# AD.net
KiCad netlist of a schematic drawn in Altium Designer
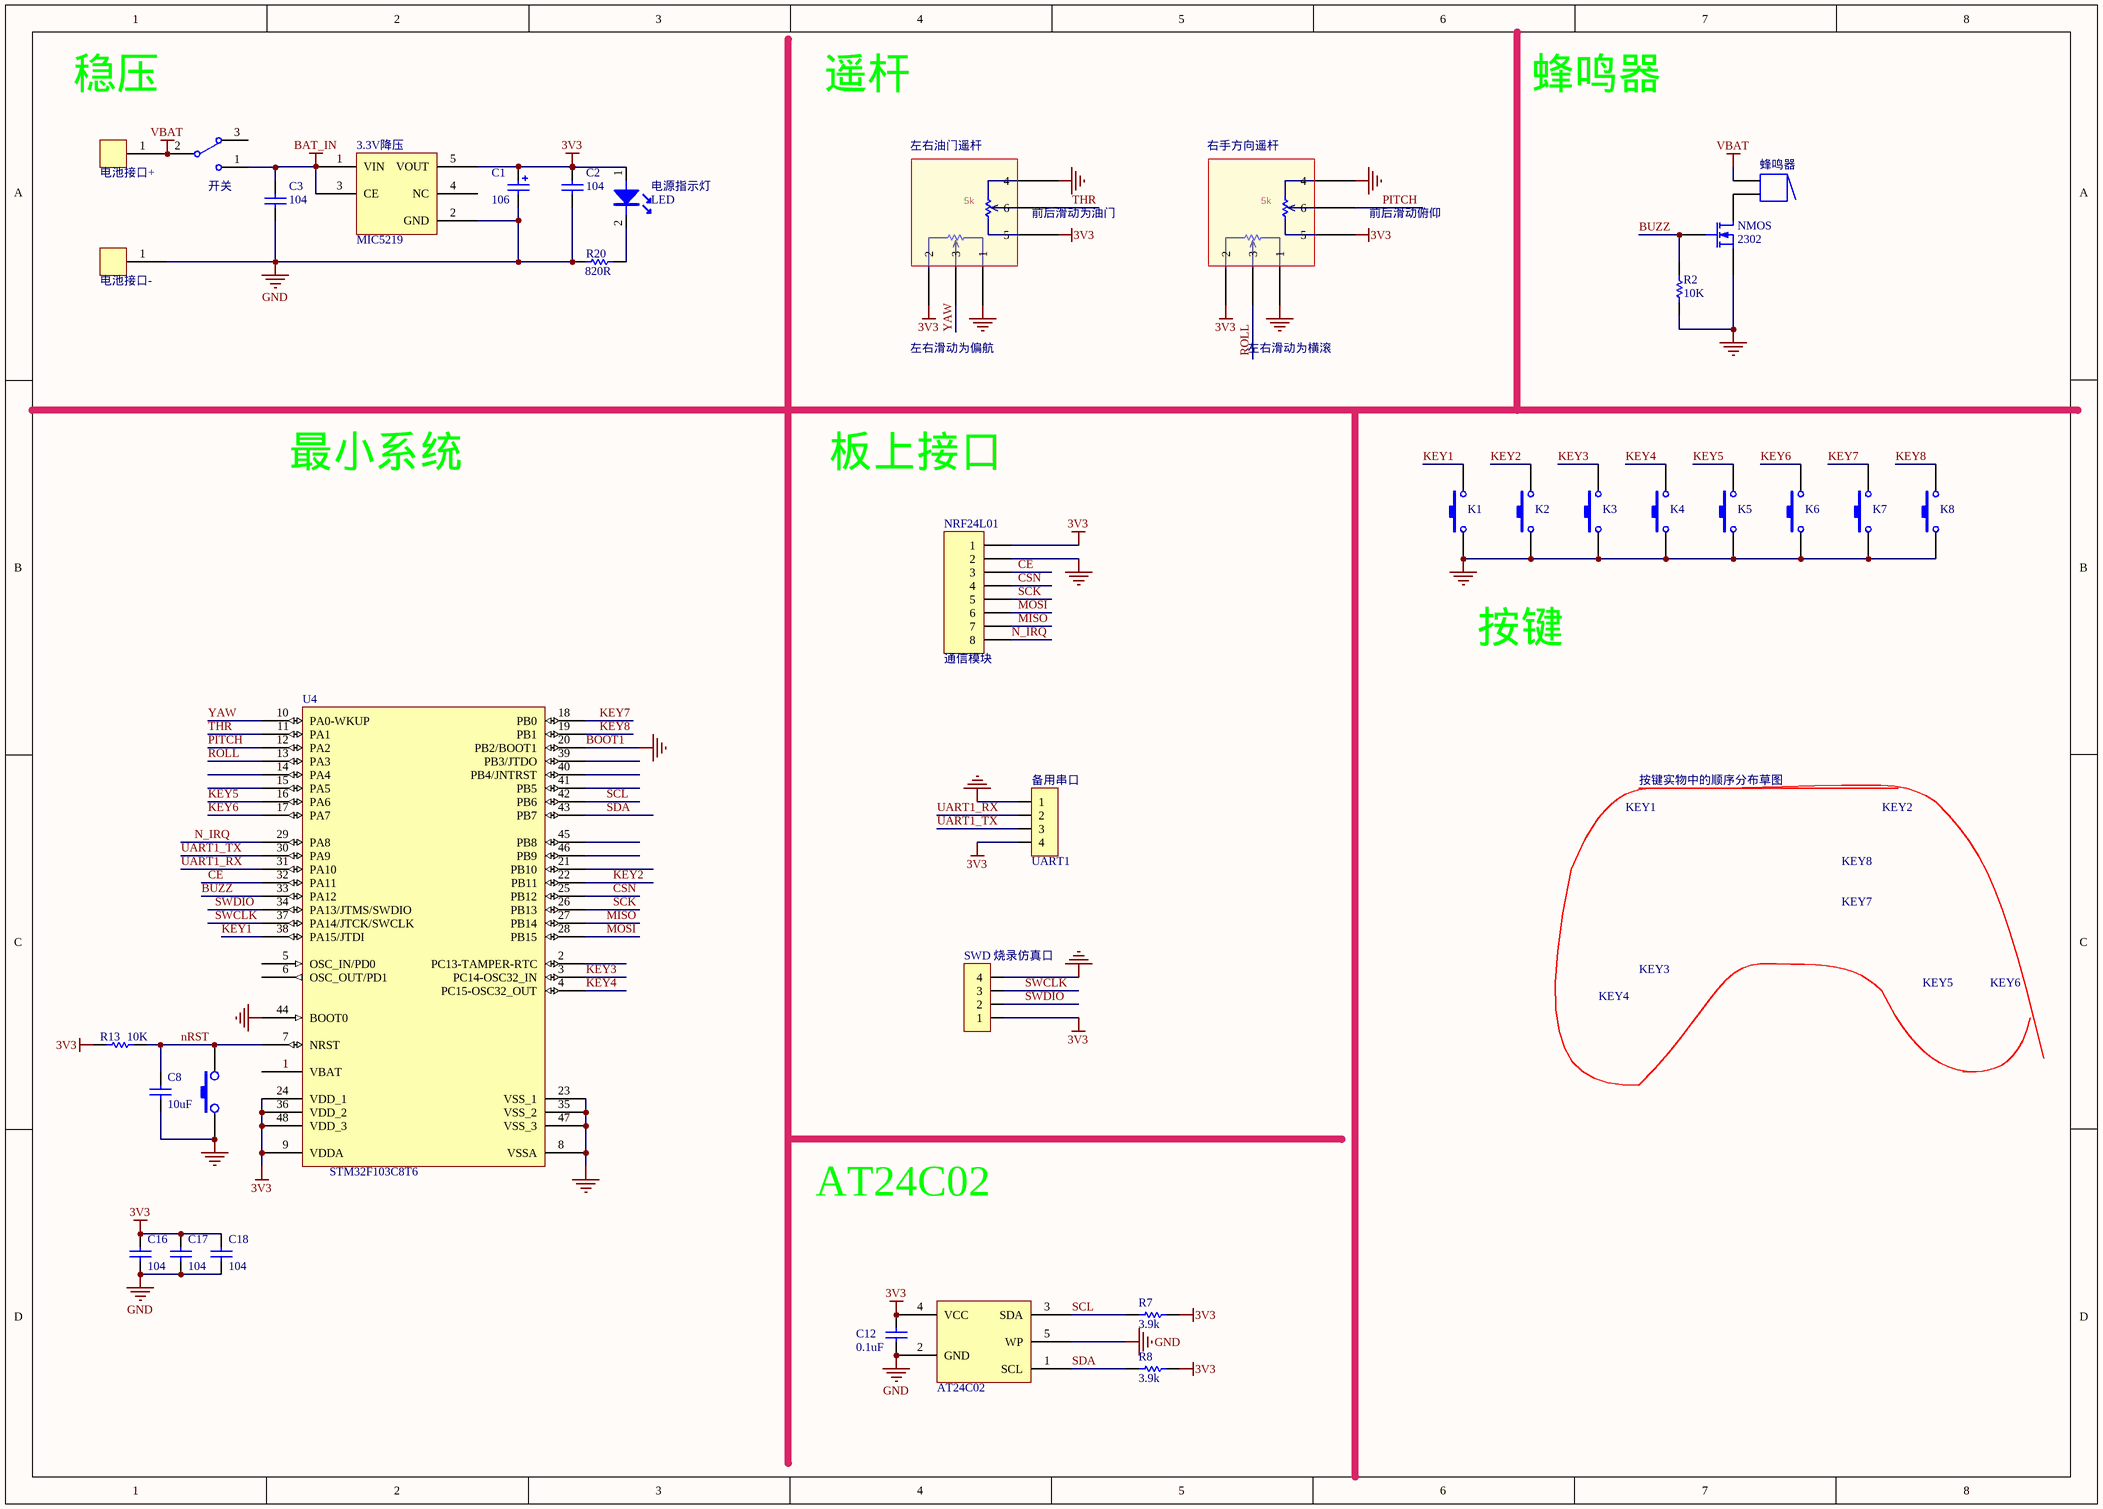
[diagram p0: 遥控原理图（AD打开）.SchDoc]

(export (version "E")
  (design (tool "Eeschema 10.0.6"))
  (components
    (comp (ref "*1") (value "AT24C02") (footprint "SOT23-5") (libsource (lib "开源小遥控") (part "AT24C02")))
    (comp (ref "3.3V降压")
      (value "MIC5219")
      (footprint "SOT23-5")
      (libsource (lib "quadrotor") (part "HT7X33"))
    )
    (comp (ref "C1")
      (value "106")
      (footprint "1206")
      (description "Polarized Capacitor (Radial)")
      (fields
        (field (name "VOLTAGE") "16V")
        (field (name "Comment") "Cap Tan A")
        (field (name "PUBLISHER") "Altium Limited")
      )
      (libsource (lib "ChapuIntegratedLibrary") (part "Cap Tan A"))
    )
    (comp (ref "C2")
      (value "104")
      (footprint "1206_C")
      (description "Polarized Capacitor (Radial)")
      (fields (field (name "Comment") "Cap Chip 1206") (field (name "PUBLISHER") "Altium Limited"))
      (libsource (lib "ChapuIntegratedLibrary") (part "Cap Chip 1206"))
    )
    (comp (ref "C3")
      (value "104")
      (footprint "0603_C")
      (description "Polarized Capacitor (Radial)")
      (fields (field (name "Comment") "Cap Chip 1206") (field (name "PUBLISHER") "Altium Limited"))
      (libsource (lib "ChapuIntegratedLibrary") (part "Cap Chip 1206"))
    )
    (comp (ref "C8") (value "10uF") (footprint "0603_C") (libsource (lib "1218迷你四轴工程_1") (part "C0603")))
    (comp (ref "C12")
      (value "0.1uF")
      (footprint "0603C")
      (description "Capacitor")
      (fields (field (name "Comment") "Cap") (field (name "PUBLISHER") "Altium Limited"))
      (libsource (lib "Miscellaneous Devices") (part "Cap"))
    )
    (comp (ref "C16") (value "104") (footprint "0603_C") (libsource (lib "1218迷你四轴工程_1") (part "C0603")))
    (comp (ref "C17") (value "104") (footprint "0603_C") (libsource (lib "1218迷你四轴工程_1") (part "C0603")))
    (comp (ref "C18") (value "104") (footprint "0603_C") (libsource (lib "1218迷你四轴工程_1") (part "C0603")))
    (comp (ref "K1")
      (value "40%（油門上限）")
      (footprint "4脚贴片点动开关")
      (description "Switch")
      (fields (field (name "PUBLISHER") "Altium Limited"))
      (libsource (lib "Miscellaneous Devices") (part "SW-PB"))
    )
    (comp (ref "K2")
      (value "60%")
      (footprint "4脚贴片点动开关")
      (description "Switch")
      (fields (field (name "PUBLISHER") "Altium Limited"))
      (libsource (lib "Miscellaneous Devices") (part "SW-PB"))
    )
    (comp (ref "K3")
      (value "40%（油門上限）")
      (footprint "4脚贴片点动开关")
      (description "Switch")
      (fields (field (name "PUBLISHER") "Altium Limited"))
      (libsource (lib "Miscellaneous Devices") (part "SW-PB"))
    )
    (comp (ref "K4")
      (value "60%")
      (footprint "4脚贴片点动开关")
      (description "Switch")
      (fields (field (name "PUBLISHER") "Altium Limited"))
      (libsource (lib "Miscellaneous Devices") (part "SW-PB"))
    )
    (comp (ref "K5")
      (value "40%（油門上限）")
      (footprint "4脚贴片点动开关")
      (description "Switch")
      (fields (field (name "PUBLISHER") "Altium Limited"))
      (libsource (lib "Miscellaneous Devices") (part "SW-PB"))
    )
    (comp (ref "K6")
      (value "60%")
      (footprint "4脚贴片点动开关")
      (description "Switch")
      (fields (field (name "PUBLISHER") "Altium Limited"))
      (libsource (lib "Miscellaneous Devices") (part "SW-PB"))
    )
    (comp (ref "K7")
      (value "40%（油門上限）")
      (footprint "4脚贴片点动开关")
      (description "Switch")
      (fields (field (name "PUBLISHER") "Altium Limited"))
      (libsource (lib "Miscellaneous Devices") (part "SW-PB"))
    )
    (comp (ref "K8")
      (value "60%")
      (footprint "4脚贴片点动开关")
      (description "Switch")
      (fields (field (name "PUBLISHER") "Altium Limited"))
      (libsource (lib "Miscellaneous Devices") (part "SW-PB"))
    )
    (comp (ref "NMOS")
      (value "2302")
      (footprint "SOT-23-3")
      (description "N-Channel MOSFET")
      (fields (field (name "PUBLISHER") "Altium Limited"))
      (libsource (lib "Miscellaneous Devices") (part "MOSFET-N"))
    )
    (comp (ref "NRF24L01")
      (value "通信模块")
      (footprint "HDR1X8")
      (description "Header, 8-Pin")
      (fields (field (name "PUBLISHER") "Altium Limited"))
      (libsource (lib "Miscellaneous Connectors") (part "Header 8"))
    )
    (comp (ref "R2")
      (value "10K")
      (footprint "0603_R")
      (description "Resistor")
      (fields (field (name "Comment") "222") (field (name "PUBLISHER") "Altium Limited"))
      (libsource (lib "Miscellaneous Devices") (part "Res1"))
    )
    (comp (ref "R7")
      (value "3.9k")
      (footprint "0603R")
      (description "Resistor")
      (fields (field (name "Comment") "222") (field (name "PUBLISHER") "Altium Limited"))
      (libsource (lib "Miscellaneous Devices") (part "Res1"))
    )
    (comp (ref "R8")
      (value "3.9k")
      (footprint "0603R")
      (description "Resistor")
      (fields (field (name "Comment") "222") (field (name "PUBLISHER") "Altium Limited"))
      (libsource (lib "Miscellaneous Devices") (part "Res1"))
    )
    (comp (ref "R13")
      (value "10K")
      (footprint "0603_R")
      (description "Resistor")
      (fields (field (name "Comment") "Res1") (field (name "PUBLISHER") "Altium Limited"))
      (libsource (lib "Miscellaneous Devices") (part "Res1"))
    )
    (comp (ref "R20")
      (value "820R")
      (footprint "0603_R")
      (description "Resistor")
      (fields (field (name "Comment") "222") (field (name "PUBLISHER") "Altium Limited"))
      (libsource (lib "Miscellaneous Devices") (part "Res1"))
    )
    (comp (ref "REST1") (value "SW-PB") (footprint "SW-2") (libsource (lib "SW开关") (part "SW-PB")))
    (comp (ref "SWD 烧录仿真口")
      (value "SWD")
      (footprint "1.27侧卧表贴")
      (description "Header, 4-Pin, Right Angle")
      (fields (field (name "PUBLISHER") "Altium Limited"))
      (libsource (lib "linch051") (part "Header 4H"))
    )
    (comp (ref "U4")
      (value "STM32F103C8T6")
      (footprint "LQFP48")
      (libsource (lib "微型四轴") (part "STM32F103C8T6"))
    )
    (comp (ref "右手方向遥杆") (value "摇杆") (footprint "遥控电位器") (libsource (lib "开源小遥控") (part "摇杆")))
    (comp (ref "备用串口")
      (value "UART1")
      (footprint "1.27侧卧表贴")
      (description "Header, 4-Pin, Right Angle")
      (fields (field (name "PUBLISHER") "Altium Limited"))
      (libsource (lib "") (part "Header 4H_1"))
    )
    (comp (ref "左右油门遥杆") (value "摇杆") (footprint "遥控电位器") (libsource (lib "开源小遥控") (part "摇杆")))
    (comp (ref "开关")
      (value "SW-SPDT")
      (footprint "SW-5")
      (description "SPDT Subminiature Toggle Switch, Right Angle Mounting, Vertical Actuation")
      (fields (field (name "PUBLISHER") "Altium Limited"))
      (libsource (lib "Miscellaneous Devices") (part "SW-SPDT"))
    )
    (comp (ref "电池接口+") (value "Header 1") (footprint "BAT") (libsource (lib "quadrotor") (part "Header 1")))
    (comp (ref "电池接口-") (value "Header 1") (footprint "BAT") (libsource (lib "quadrotor") (part "Header 1")))
    (comp (ref "电源指示灯") (value "LED") (footprint "0603_LED") (libsource (lib "1218迷你四轴工程_1") (part "LED")))
    (comp (ref "蜂鸣器")
      (value "Buzzer")
      (footprint "蜂鸣器9mm")
      (description "Magnetic Transducer Buzzer")
      (fields (field (name "PUBLISHER") "Altium Limited"))
      (libsource (lib "PCB_Project1") (part "Buzzer"))
    )
  )
  (nets
    (net (code "1") (name "/BUZZ") (class "Default")
      (node (ref "NMOS") (pin "2") (pinfunction "G_2") (pintype "passive"))
      (node (ref "R2") (pin "1") (pinfunction "1_1") (pintype "passive"))
      (node (ref "U4") (pin "33") (pinfunction "PA12_33") (pintype "bidirectional"))
    )
    (net (code "2") (name "/CE") (class "Default")
      (node (ref "NRF24L01") (pin "3") (pinfunction "3_3") (pintype "passive"))
      (node (ref "U4") (pin "32") (pinfunction "PA11_32") (pintype "bidirectional"))
    )
    (net (code "3") (name "/CSN") (class "Default")
      (node (ref "NRF24L01") (pin "4") (pinfunction "4_4") (pintype "passive"))
      (node (ref "U4") (pin "25") (pinfunction "PB12_25") (pintype "bidirectional"))
    )
    (net (code "4") (name "/KEY1") (class "Default")
      (node (ref "K1") (pin "2") (pinfunction "2_2") (pintype "passive"))
      (node (ref "U4") (pin "38") (pinfunction "PA15/JTDI_38") (pintype "bidirectional"))
    )
    (net (code "5") (name "/KEY2") (class "Default")
      (node (ref "K2") (pin "2") (pinfunction "2_2") (pintype "passive"))
      (node (ref "U4") (pin "22") (pinfunction "PB11_22") (pintype "bidirectional"))
    )
    (net (code "6") (name "/KEY3") (class "Default")
      (node (ref "K3") (pin "2") (pinfunction "2_2") (pintype "passive"))
      (node (ref "U4") (pin "3") (pinfunction "PC14-OSC32_IN_3") (pintype "bidirectional"))
    )
    (net (code "7") (name "/KEY4") (class "Default")
      (node (ref "K4") (pin "2") (pinfunction "2_2") (pintype "passive"))
      (node (ref "U4") (pin "4") (pinfunction "PC15-OSC32_OUT_4") (pintype "bidirectional"))
    )
    (net (code "8") (name "/KEY5") (class "Default")
      (node (ref "K5") (pin "2") (pinfunction "2_2") (pintype "passive"))
      (node (ref "U4") (pin "16") (pinfunction "PA6_16") (pintype "bidirectional"))
    )
    (net (code "9") (name "/KEY6") (class "Default")
      (node (ref "K6") (pin "2") (pinfunction "2_2") (pintype "passive"))
      (node (ref "U4") (pin "17") (pinfunction "PA7_17") (pintype "bidirectional"))
    )
    (net (code "10") (name "/KEY7") (class "Default")
      (node (ref "K7") (pin "2") (pinfunction "2_2") (pintype "passive"))
      (node (ref "U4") (pin "18") (pinfunction "PB0_18") (pintype "bidirectional"))
    )
    (net (code "11") (name "/KEY8") (class "Default")
      (node (ref "K8") (pin "2") (pinfunction "2_2") (pintype "passive"))
      (node (ref "U4") (pin "19") (pinfunction "PB1_19") (pintype "bidirectional"))
    )
    (net (code "12") (name "/MISO") (class "Default")
      (node (ref "NRF24L01") (pin "7") (pinfunction "7_7") (pintype "passive"))
      (node (ref "U4") (pin "27") (pinfunction "PB14_27") (pintype "bidirectional"))
    )
    (net (code "13") (name "/MOSI") (class "Default")
      (node (ref "NRF24L01") (pin "6") (pinfunction "6_6") (pintype "passive"))
      (node (ref "U4") (pin "28") (pinfunction "PB15_28") (pintype "bidirectional"))
    )
    (net (code "14") (name "/N_IRQ") (class "Default")
      (node (ref "NRF24L01") (pin "8") (pinfunction "8_8") (pintype "passive"))
      (node (ref "U4") (pin "29") (pinfunction "PA8_29") (pintype "bidirectional"))
    )
    (net (code "15") (name "/PITCH") (class "Default")
      (node (ref "U4") (pin "12") (pinfunction "PA2_12") (pintype "bidirectional"))
      (node (ref "右手方向遥杆") (pin "6") (pinfunction "6_6") (pintype "passive"))
    )
    (net (code "16") (name "/ROLL") (class "Default")
      (node (ref "U4") (pin "13") (pinfunction "PA3_13") (pintype "bidirectional"))
      (node (ref "右手方向遥杆") (pin "3") (pinfunction "3_3") (pintype "passive"))
    )
    (net (code "17") (name "/SCK") (class "Default")
      (node (ref "NRF24L01") (pin "5") (pinfunction "5_5") (pintype "passive"))
      (node (ref "U4") (pin "26") (pinfunction "PB13_26") (pintype "bidirectional"))
    )
    (net (code "18") (name "/SCL") (class "Default")
      (node (ref "*1") (pin "3") (pinfunction "SDA_3") (pintype "passive"))
      (node (ref "R7") (pin "1") (pinfunction "1_1") (pintype "passive"))
      (node (ref "U4") (pin "42") (pinfunction "PB6_42") (pintype "bidirectional"))
    )
    (net (code "19") (name "/SDA") (class "Default")
      (node (ref "*1") (pin "1") (pinfunction "SCL_1") (pintype "passive"))
      (node (ref "R8") (pin "1") (pinfunction "1_1") (pintype "passive"))
      (node (ref "U4") (pin "43") (pinfunction "PB7_43") (pintype "bidirectional"))
    )
    (net (code "20") (name "/SWCLK") (class "Default")
      (node (ref "SWD 烧录仿真口") (pin "3") (pinfunction "3_3") (pintype "passive"))
      (node (ref "U4") (pin "37") (pinfunction "PA14/JTCK/SWCLK_37") (pintype "bidirectional"))
    )
    (net (code "21") (name "/SWDIO") (class "Default")
      (node (ref "SWD 烧录仿真口") (pin "2") (pinfunction "2_2") (pintype "passive"))
      (node (ref "U4") (pin "34") (pinfunction "PA13/JTMS/SWDIO_34") (pintype "bidirectional"))
    )
    (net (code "22") (name "/THR") (class "Default")
      (node (ref "U4") (pin "11") (pinfunction "PA1_11") (pintype "bidirectional"))
      (node (ref "左右油门遥杆") (pin "6") (pinfunction "6_6") (pintype "passive"))
    )
    (net (code "23") (name "/UART1_RX") (class "Default")
      (node (ref "U4") (pin "31") (pinfunction "PA10_31") (pintype "bidirectional"))
      (node (ref "备用串口") (pin "2") (pinfunction "2_2") (pintype "passive"))
    )
    (net (code "24") (name "/UART1_TX") (class "Default")
      (node (ref "U4") (pin "30") (pinfunction "PA9_30") (pintype "bidirectional"))
      (node (ref "备用串口") (pin "3") (pinfunction "3_3") (pintype "passive"))
    )
    (net (code "25") (name "/YAW") (class "Default")
      (node (ref "U4") (pin "10") (pinfunction "PA0-WKUP_10") (pintype "bidirectional"))
      (node (ref "左右油门遥杆") (pin "3") (pinfunction "3_3") (pintype "passive"))
    )
    (net (code "26") (name "/nRST") (class "Default")
      (node (ref "C8") (pin "1") (pinfunction "1_1") (pintype "passive"))
      (node (ref "R13") (pin "1") (pinfunction "1_1") (pintype "passive"))
      (node (ref "REST1") (pin "2") (pinfunction "2_2") (pintype "passive"))
      (node (ref "U4") (pin "7") (pinfunction "NRST_7") (pintype "bidirectional"))
    )
    (net (code "27") (name "3V3") (class "Default")
      (node (ref "*1") (pin "4") (pinfunction "VCC_4") (pintype "passive"))
      (node (ref "3.3V降压") (pin "5") (pinfunction "VOUT_5") (pintype "passive"))
      (node (ref "C1") (pin "2") (pinfunction "1_2") (pintype "passive"))
      (node (ref "C12") (pin "1") (pinfunction "1_1") (pintype "passive"))
      (node (ref "C16") (pin "1") (pinfunction "1_1") (pintype "passive"))
      (node (ref "C17") (pin "1") (pinfunction "1_1") (pintype "passive"))
      (node (ref "C18") (pin "1") (pinfunction "1_1") (pintype "passive"))
      (node (ref "C2") (pin "1") (pinfunction "1_1") (pintype "passive"))
      (node (ref "NRF24L01") (pin "1") (pinfunction "1_1") (pintype "passive"))
      (node (ref "R13") (pin "2") (pinfunction "2_2") (pintype "passive"))
      (node (ref "R7") (pin "2") (pinfunction "2_2") (pintype "passive"))
      (node (ref "R8") (pin "2") (pinfunction "2_2") (pintype "passive"))
      (node (ref "SWD 烧录仿真口") (pin "1") (pinfunction "1_1") (pintype "passive"))
      (node (ref "U4") (pin "24") (pinfunction "VDD_1_24") (pintype "power_in"))
      (node (ref "U4") (pin "36") (pinfunction "VDD_2_36") (pintype "power_in"))
      (node (ref "U4") (pin "48") (pinfunction "VDD_3_48") (pintype "power_in"))
      (node (ref "U4") (pin "9") (pinfunction "VDDA_9") (pintype "power_in"))
      (node (ref "右手方向遥杆") (pin "2") (pinfunction "2_2") (pintype "passive"))
      (node (ref "右手方向遥杆") (pin "5") (pinfunction "5_5") (pintype "passive"))
      (node (ref "备用串口") (pin "4") (pinfunction "4_4") (pintype "passive"))
      (node (ref "左右油门遥杆") (pin "2") (pinfunction "2_2") (pintype "passive"))
      (node (ref "左右油门遥杆") (pin "5") (pinfunction "5_5") (pintype "passive"))
      (node (ref "电源指示灯") (pin "1") (pinfunction "1_1") (pintype "passive"))
    )
    (net (code "28") (name "BAT_IN") (class "Default")
      (node (ref "3.3V降压") (pin "1") (pinfunction "VIN_1") (pintype "passive"))
      (node (ref "3.3V降压") (pin "3") (pinfunction "CE_3") (pintype "passive"))
      (node (ref "C3") (pin "1") (pinfunction "1_1") (pintype "passive"))
      (node (ref "开关") (pin "1") (pinfunction "1_1") (pintype "passive"))
    )
    (net (code "29") (name "GND") (class "Default")
      (node (ref "*1") (pin "2") (pinfunction "GND_2") (pintype "passive"))
      (node (ref "*1") (pin "5") (pinfunction "WP_5") (pintype "passive"))
      (node (ref "3.3V降压") (pin "2") (pinfunction "GND_2") (pintype "passive"))
      (node (ref "C1") (pin "1") (pinfunction "2_1") (pintype "passive"))
      (node (ref "C12") (pin "2") (pinfunction "2_2") (pintype "passive"))
      (node (ref "C16") (pin "2") (pinfunction "2_2") (pintype "passive"))
      (node (ref "C17") (pin "2") (pinfunction "2_2") (pintype "passive"))
      (node (ref "C18") (pin "2") (pinfunction "2_2") (pintype "passive"))
      (node (ref "C2") (pin "2") (pinfunction "2_2") (pintype "passive"))
      (node (ref "C3") (pin "2") (pinfunction "2_2") (pintype "passive"))
      (node (ref "C8") (pin "2") (pinfunction "2_2") (pintype "passive"))
      (node (ref "K1") (pin "1") (pinfunction "1_1") (pintype "passive"))
      (node (ref "K2") (pin "1") (pinfunction "1_1") (pintype "passive"))
      (node (ref "K3") (pin "1") (pinfunction "1_1") (pintype "passive"))
      (node (ref "K4") (pin "1") (pinfunction "1_1") (pintype "passive"))
      (node (ref "K5") (pin "1") (pinfunction "1_1") (pintype "passive"))
      (node (ref "K6") (pin "1") (pinfunction "1_1") (pintype "passive"))
      (node (ref "K7") (pin "1") (pinfunction "1_1") (pintype "passive"))
      (node (ref "K8") (pin "1") (pinfunction "1_1") (pintype "passive"))
      (node (ref "NMOS") (pin "3") (pinfunction "S_3") (pintype "passive"))
      (node (ref "NRF24L01") (pin "2") (pinfunction "2_2") (pintype "passive"))
      (node (ref "R2") (pin "2") (pinfunction "2_2") (pintype "passive"))
      (node (ref "R20") (pin "1") (pinfunction "1_1") (pintype "passive"))
      (node (ref "REST1") (pin "1") (pinfunction "1_1") (pintype "passive"))
      (node (ref "SWD 烧录仿真口") (pin "4") (pinfunction "4_4") (pintype "passive"))
      (node (ref "U4") (pin "20") (pinfunction "PB2/BOOT1_20") (pintype "bidirectional"))
      (node (ref "U4") (pin "23") (pinfunction "VSS_1_23") (pintype "power_in"))
      (node (ref "U4") (pin "35") (pinfunction "VSS_2_35") (pintype "power_in"))
      (node (ref "U4") (pin "44") (pinfunction "BOOT0_44") (pintype "input"))
      (node (ref "U4") (pin "47") (pinfunction "VSS_3_47") (pintype "power_in"))
      (node (ref "U4") (pin "8") (pinfunction "VSSA_8") (pintype "power_in"))
      (node (ref "右手方向遥杆") (pin "1") (pinfunction "1_1") (pintype "passive"))
      (node (ref "右手方向遥杆") (pin "4") (pinfunction "4_4") (pintype "passive"))
      (node (ref "备用串口") (pin "1") (pinfunction "1_1") (pintype "passive"))
      (node (ref "左右油门遥杆") (pin "1") (pinfunction "1_1") (pintype "passive"))
      (node (ref "左右油门遥杆") (pin "4") (pinfunction "4_4") (pintype "passive"))
      (node (ref "电池接口-") (pin "1") (pintype "passive"))
    )
    (net (code "30") (name "Net-(NMOS-D)") (class "Default")
      (node (ref "NMOS") (pin "1") (pinfunction "D_1") (pintype "passive"))
      (node (ref "蜂鸣器") (pin "1") (pinfunction "1_1") (pintype "passive"))
    )
    (net (code "31") (name "Net-(R20-Pad2)") (class "Default")
      (node (ref "R20") (pin "2") (pinfunction "2_2") (pintype "passive"))
      (node (ref "电源指示灯") (pin "2") (pinfunction "2_2") (pintype "passive"))
    )
    (net (code "32") (name "VBAT") (class "Default")
      (node (ref "开关") (pin "2") (pinfunction "2_2") (pintype "passive"))
      (node (ref "电池接口+") (pin "1") (pintype "passive"))
      (node (ref "蜂鸣器") (pin "2") (pinfunction "2_2") (pintype "passive"))
    )
    (net (code "33") (name "unconnected-(3.3V降压-NC-Pad4)") (class "Default")
      (node (ref "3.3V降压") (pin "4") (pinfunction "NC_4") (pintype "passive"))
    )
    (net (code "34") (name "unconnected-(U4-OSC_IN{slash}PD0-Pad5)") (class "Default")
      (node (ref "U4") (pin "5") (pinfunction "OSC_IN/PD0_5") (pintype "input"))
    )
    (net (code "35") (name "unconnected-(U4-OSC_OUT{slash}PD1-Pad6)") (class "Default")
      (node (ref "U4") (pin "6") (pinfunction "OSC_OUT/PD1_6") (pintype "output"))
    )
    (net (code "36") (name "unconnected-(U4-PA4-Pad14)") (class "Default")
      (node (ref "U4") (pin "14") (pinfunction "PA4_14") (pintype "bidirectional"))
    )
    (net (code "37") (name "unconnected-(U4-PA5-Pad15)") (class "Default")
      (node (ref "U4") (pin "15") (pinfunction "PA5_15") (pintype "bidirectional"))
    )
    (net (code "38") (name "unconnected-(U4-PB3{slash}JTDO-Pad39)") (class "Default")
      (node (ref "U4") (pin "39") (pinfunction "PB3/JTDO_39") (pintype "bidirectional"))
    )
    (net (code "39") (name "unconnected-(U4-PB4{slash}JNTRST-Pad40)") (class "Default")
      (node (ref "U4") (pin "40") (pinfunction "PB4/JNTRST_40") (pintype "bidirectional"))
    )
    (net (code "40") (name "unconnected-(U4-PB5-Pad41)") (class "Default")
      (node (ref "U4") (pin "41") (pinfunction "PB5_41") (pintype "bidirectional"))
    )
    (net (code "41") (name "unconnected-(U4-PB8-Pad45)") (class "Default")
      (node (ref "U4") (pin "45") (pinfunction "PB8_45") (pintype "bidirectional"))
    )
    (net (code "42") (name "unconnected-(U4-PB9-Pad46)") (class "Default")
      (node (ref "U4") (pin "46") (pinfunction "PB9_46") (pintype "bidirectional"))
    )
    (net (code "43") (name "unconnected-(U4-PB10-Pad21)") (class "Default")
      (node (ref "U4") (pin "21") (pinfunction "PB10_21") (pintype "bidirectional"))
    )
    (net (code "44") (name "unconnected-(U4-PC13-TAMPER-RTC-Pad2)") (class "Default")
      (node (ref "U4") (pin "2") (pinfunction "PC13-TAMPER-RTC_2") (pintype "bidirectional"))
    )
    (net (code "45") (name "unconnected-(U4-VBAT-Pad1)") (class "Default")
      (node (ref "U4") (pin "1") (pinfunction "VBAT_1") (pintype "power_in"))
    )
    (net (code "46") (name "unconnected-(开关-Pad3)") (class "Default")
      (node (ref "开关") (pin "3") (pinfunction "3_3") (pintype "passive"))
    )
  )
)
